# PCBSchematic.net
KiCad netlist of a schematic drawn in Altium Designer
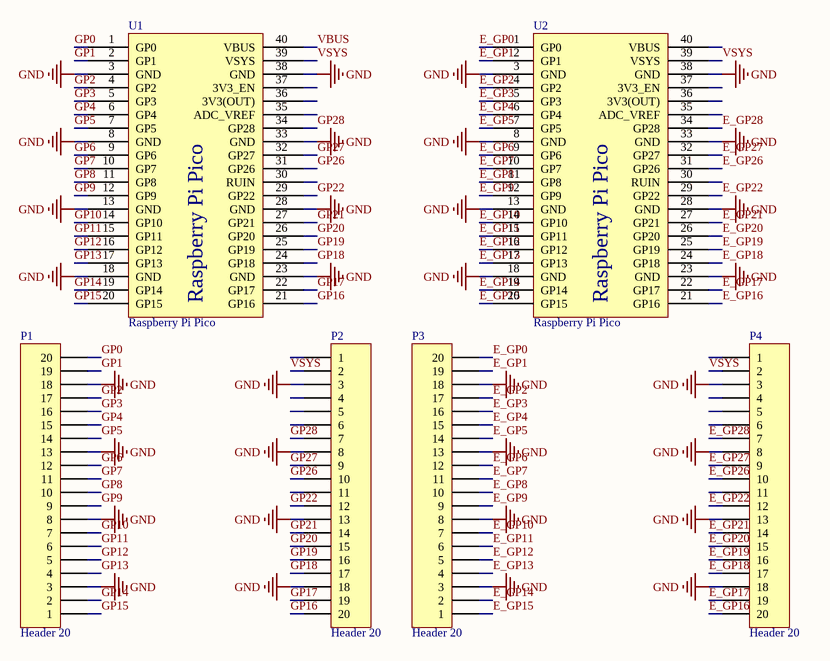
[diagram p0: PCBSchematic.SchDoc]

(export (version "E")
  (design (tool "Eeschema 10.0.6"))
  (components
    (comp (ref "P1")
      (value "Header 20")
      (footprint "HDR1X20")
      (description "Header, 20-Pin")
      (fields (field (name "PUBLISHER") "Altium Limited"))
      (libsource (lib "Miscellaneous Connectors") (part "Header 20"))
    )
    (comp (ref "P2")
      (value "Header 20")
      (footprint "HDR1X20")
      (description "Header, 20-Pin")
      (fields (field (name "PUBLISHER") "Altium Limited"))
      (libsource (lib "") (part "Header 20_1"))
    )
    (comp (ref "P3")
      (value "Header 20")
      (footprint "HDR1X20")
      (description "Header, 20-Pin")
      (fields (field (name "PUBLISHER") "Altium Limited"))
      (libsource (lib "Miscellaneous Connectors") (part "Header 20"))
    )
    (comp (ref "P4")
      (value "Header 20")
      (footprint "HDR1X20")
      (description "Header, 20-Pin")
      (fields (field (name "PUBLISHER") "Altium Limited"))
      (libsource (lib "") (part "Header 20_1"))
    )
    (comp (ref "U1")
      (value "Raspberry Pi Pico")
      (footprint "Raspberry Pi Pico")
      (libsource (lib "ECE Lib 22") (part "Raspberry Pi Pico"))
    )
    (comp (ref "U2")
      (value "Raspberry Pi Pico")
      (footprint "Raspberry Pi Pico")
      (libsource (lib "ECE Lib 22") (part "Raspberry Pi Pico"))
    )
  )
  (nets
    (net (code "1") (name "/E_GP0") (class "Default")
      (node (ref "P3") (pin "20") (pinfunction "20_20") (pintype "passive"))
      (node (ref "U2") (pin "1") (pinfunction "GP0_1") (pintype "passive"))
    )
    (net (code "2") (name "/E_GP1") (class "Default")
      (node (ref "P3") (pin "19") (pinfunction "19_19") (pintype "passive"))
      (node (ref "U2") (pin "2") (pinfunction "GP1_2") (pintype "passive"))
    )
    (net (code "3") (name "/E_GP2") (class "Default")
      (node (ref "P3") (pin "17") (pinfunction "17_17") (pintype "passive"))
      (node (ref "U2") (pin "4") (pinfunction "GP2_4") (pintype "passive"))
    )
    (net (code "4") (name "/E_GP3") (class "Default")
      (node (ref "P3") (pin "16") (pinfunction "16_16") (pintype "passive"))
      (node (ref "U2") (pin "5") (pinfunction "GP3_5") (pintype "passive"))
    )
    (net (code "5") (name "/E_GP4") (class "Default")
      (node (ref "P3") (pin "15") (pinfunction "15_15") (pintype "passive"))
      (node (ref "U2") (pin "6") (pinfunction "GP4_6") (pintype "passive"))
    )
    (net (code "6") (name "/E_GP5") (class "Default")
      (node (ref "P3") (pin "14") (pinfunction "14_14") (pintype "passive"))
      (node (ref "U2") (pin "7") (pinfunction "GP5_7") (pintype "passive"))
    )
    (net (code "7") (name "/E_GP6") (class "Default")
      (node (ref "P3") (pin "12") (pinfunction "12_12") (pintype "passive"))
      (node (ref "U2") (pin "9") (pinfunction "GP6_9") (pintype "passive"))
    )
    (net (code "8") (name "/E_GP7") (class "Default")
      (node (ref "P3") (pin "11") (pinfunction "11_11") (pintype "passive"))
      (node (ref "U2") (pin "10") (pinfunction "GP7_10") (pintype "passive"))
    )
    (net (code "9") (name "/E_GP8") (class "Default")
      (node (ref "P3") (pin "10") (pinfunction "10_10") (pintype "passive"))
      (node (ref "U2") (pin "11") (pinfunction "GP8_11") (pintype "passive"))
    )
    (net (code "10") (name "/E_GP9") (class "Default")
      (node (ref "P3") (pin "9") (pinfunction "9_9") (pintype "passive"))
      (node (ref "U2") (pin "12") (pinfunction "GP9_12") (pintype "passive"))
    )
    (net (code "11") (name "/E_GP10") (class "Default")
      (node (ref "P3") (pin "7") (pinfunction "7_7") (pintype "passive"))
      (node (ref "U2") (pin "14") (pinfunction "GP10_14") (pintype "passive"))
    )
    (net (code "12") (name "/E_GP11") (class "Default")
      (node (ref "P3") (pin "6") (pinfunction "6_6") (pintype "passive"))
      (node (ref "U2") (pin "15") (pinfunction "GP11_15") (pintype "passive"))
    )
    (net (code "13") (name "/E_GP12") (class "Default")
      (node (ref "P3") (pin "5") (pinfunction "5_5") (pintype "passive"))
      (node (ref "U2") (pin "16") (pinfunction "GP12_16") (pintype "passive"))
    )
    (net (code "14") (name "/E_GP13") (class "Default")
      (node (ref "P3") (pin "4") (pinfunction "4_4") (pintype "passive"))
      (node (ref "U2") (pin "17") (pinfunction "GP13_17") (pintype "passive"))
    )
    (net (code "15") (name "/E_GP14") (class "Default")
      (node (ref "P3") (pin "2") (pinfunction "2_2") (pintype "passive"))
      (node (ref "U2") (pin "19") (pinfunction "GP14_19") (pintype "passive"))
    )
    (net (code "16") (name "/E_GP15") (class "Default")
      (node (ref "P3") (pin "1") (pinfunction "1_1") (pintype "passive"))
      (node (ref "U2") (pin "20") (pinfunction "GP15_20") (pintype "passive"))
    )
    (net (code "17") (name "/E_GP16") (class "Default")
      (node (ref "P4") (pin "20") (pinfunction "20_20") (pintype "passive"))
      (node (ref "U2") (pin "21") (pinfunction "GP16_21") (pintype "passive"))
    )
    (net (code "18") (name "/E_GP17") (class "Default")
      (node (ref "P4") (pin "19") (pinfunction "19_19") (pintype "passive"))
      (node (ref "U2") (pin "22") (pinfunction "GP17_22") (pintype "passive"))
    )
    (net (code "19") (name "/E_GP18") (class "Default")
      (node (ref "P4") (pin "17") (pinfunction "17_17") (pintype "passive"))
      (node (ref "U2") (pin "24") (pinfunction "GP18_24") (pintype "passive"))
    )
    (net (code "20") (name "/E_GP19") (class "Default")
      (node (ref "P4") (pin "16") (pinfunction "16_16") (pintype "passive"))
      (node (ref "U2") (pin "25") (pinfunction "GP19_25") (pintype "passive"))
    )
    (net (code "21") (name "/E_GP20") (class "Default")
      (node (ref "P4") (pin "15") (pinfunction "15_15") (pintype "passive"))
      (node (ref "U2") (pin "26") (pinfunction "GP20_26") (pintype "passive"))
    )
    (net (code "22") (name "/E_GP21") (class "Default")
      (node (ref "P4") (pin "14") (pinfunction "14_14") (pintype "passive"))
      (node (ref "U2") (pin "27") (pinfunction "GP21_27") (pintype "passive"))
    )
    (net (code "23") (name "/E_GP22") (class "Default")
      (node (ref "P4") (pin "12") (pinfunction "12_12") (pintype "passive"))
      (node (ref "U2") (pin "29") (pinfunction "GP22_29") (pintype "passive"))
    )
    (net (code "24") (name "/E_GP26") (class "Default")
      (node (ref "P4") (pin "10") (pinfunction "10_10") (pintype "passive"))
      (node (ref "U2") (pin "31") (pinfunction "GP26_31") (pintype "passive"))
    )
    (net (code "25") (name "/E_GP27") (class "Default")
      (node (ref "P4") (pin "9") (pinfunction "9_9") (pintype "passive"))
      (node (ref "U2") (pin "32") (pinfunction "GP27_32") (pintype "passive"))
    )
    (net (code "26") (name "/E_GP28") (class "Default")
      (node (ref "P4") (pin "7") (pinfunction "7_7") (pintype "passive"))
      (node (ref "U2") (pin "34") (pinfunction "GP28_34") (pintype "passive"))
    )
    (net (code "27") (name "/GP0") (class "Default")
      (node (ref "P1") (pin "20") (pinfunction "20_20") (pintype "passive"))
      (node (ref "U1") (pin "1") (pinfunction "GP0_1") (pintype "passive"))
    )
    (net (code "28") (name "/GP1") (class "Default")
      (node (ref "P1") (pin "19") (pinfunction "19_19") (pintype "passive"))
      (node (ref "U1") (pin "2") (pinfunction "GP1_2") (pintype "passive"))
    )
    (net (code "29") (name "/GP2") (class "Default")
      (node (ref "P1") (pin "17") (pinfunction "17_17") (pintype "passive"))
      (node (ref "U1") (pin "4") (pinfunction "GP2_4") (pintype "passive"))
    )
    (net (code "30") (name "/GP3") (class "Default")
      (node (ref "P1") (pin "16") (pinfunction "16_16") (pintype "passive"))
      (node (ref "U1") (pin "5") (pinfunction "GP3_5") (pintype "passive"))
    )
    (net (code "31") (name "/GP4") (class "Default")
      (node (ref "P1") (pin "15") (pinfunction "15_15") (pintype "passive"))
      (node (ref "U1") (pin "6") (pinfunction "GP4_6") (pintype "passive"))
    )
    (net (code "32") (name "/GP5") (class "Default")
      (node (ref "P1") (pin "14") (pinfunction "14_14") (pintype "passive"))
      (node (ref "U1") (pin "7") (pinfunction "GP5_7") (pintype "passive"))
    )
    (net (code "33") (name "/GP6") (class "Default")
      (node (ref "P1") (pin "12") (pinfunction "12_12") (pintype "passive"))
      (node (ref "U1") (pin "9") (pinfunction "GP6_9") (pintype "passive"))
    )
    (net (code "34") (name "/GP7") (class "Default")
      (node (ref "P1") (pin "11") (pinfunction "11_11") (pintype "passive"))
      (node (ref "U1") (pin "10") (pinfunction "GP7_10") (pintype "passive"))
    )
    (net (code "35") (name "/GP8") (class "Default")
      (node (ref "P1") (pin "10") (pinfunction "10_10") (pintype "passive"))
      (node (ref "U1") (pin "11") (pinfunction "GP8_11") (pintype "passive"))
    )
    (net (code "36") (name "/GP9") (class "Default")
      (node (ref "P1") (pin "9") (pinfunction "9_9") (pintype "passive"))
      (node (ref "U1") (pin "12") (pinfunction "GP9_12") (pintype "passive"))
    )
    (net (code "37") (name "/GP10") (class "Default")
      (node (ref "P1") (pin "7") (pinfunction "7_7") (pintype "passive"))
      (node (ref "U1") (pin "14") (pinfunction "GP10_14") (pintype "passive"))
    )
    (net (code "38") (name "/GP11") (class "Default")
      (node (ref "P1") (pin "6") (pinfunction "6_6") (pintype "passive"))
      (node (ref "U1") (pin "15") (pinfunction "GP11_15") (pintype "passive"))
    )
    (net (code "39") (name "/GP12") (class "Default")
      (node (ref "P1") (pin "5") (pinfunction "5_5") (pintype "passive"))
      (node (ref "U1") (pin "16") (pinfunction "GP12_16") (pintype "passive"))
    )
    (net (code "40") (name "/GP13") (class "Default")
      (node (ref "P1") (pin "4") (pinfunction "4_4") (pintype "passive"))
      (node (ref "U1") (pin "17") (pinfunction "GP13_17") (pintype "passive"))
    )
    (net (code "41") (name "/GP14") (class "Default")
      (node (ref "P1") (pin "2") (pinfunction "2_2") (pintype "passive"))
      (node (ref "U1") (pin "19") (pinfunction "GP14_19") (pintype "passive"))
    )
    (net (code "42") (name "/GP15") (class "Default")
      (node (ref "P1") (pin "1") (pinfunction "1_1") (pintype "passive"))
      (node (ref "U1") (pin "20") (pinfunction "GP15_20") (pintype "passive"))
    )
    (net (code "43") (name "/GP16") (class "Default")
      (node (ref "P2") (pin "20") (pinfunction "20_20") (pintype "passive"))
      (node (ref "U1") (pin "21") (pinfunction "GP16_21") (pintype "passive"))
    )
    (net (code "44") (name "/GP17") (class "Default")
      (node (ref "P2") (pin "19") (pinfunction "19_19") (pintype "passive"))
      (node (ref "U1") (pin "22") (pinfunction "GP17_22") (pintype "passive"))
    )
    (net (code "45") (name "/GP18") (class "Default")
      (node (ref "P2") (pin "17") (pinfunction "17_17") (pintype "passive"))
      (node (ref "U1") (pin "24") (pinfunction "GP18_24") (pintype "passive"))
    )
    (net (code "46") (name "/GP19") (class "Default")
      (node (ref "P2") (pin "16") (pinfunction "16_16") (pintype "passive"))
      (node (ref "U1") (pin "25") (pinfunction "GP19_25") (pintype "passive"))
    )
    (net (code "47") (name "/GP20") (class "Default")
      (node (ref "P2") (pin "15") (pinfunction "15_15") (pintype "passive"))
      (node (ref "U1") (pin "26") (pinfunction "GP20_26") (pintype "passive"))
    )
    (net (code "48") (name "/GP21") (class "Default")
      (node (ref "P2") (pin "14") (pinfunction "14_14") (pintype "passive"))
      (node (ref "U1") (pin "27") (pinfunction "GP21_27") (pintype "passive"))
    )
    (net (code "49") (name "/GP22") (class "Default")
      (node (ref "P2") (pin "12") (pinfunction "12_12") (pintype "passive"))
      (node (ref "U1") (pin "29") (pinfunction "GP22_29") (pintype "passive"))
    )
    (net (code "50") (name "/GP26") (class "Default")
      (node (ref "P2") (pin "10") (pinfunction "10_10") (pintype "passive"))
      (node (ref "U1") (pin "31") (pinfunction "GP26_31") (pintype "passive"))
    )
    (net (code "51") (name "/GP27") (class "Default")
      (node (ref "P2") (pin "9") (pinfunction "9_9") (pintype "passive"))
      (node (ref "U1") (pin "32") (pinfunction "GP27_32") (pintype "passive"))
    )
    (net (code "52") (name "/GP28") (class "Default")
      (node (ref "P2") (pin "7") (pinfunction "7_7") (pintype "passive"))
      (node (ref "U1") (pin "34") (pinfunction "GP28_34") (pintype "passive"))
    )
    (net (code "53") (name "/VBUS") (class "Default")
      (node (ref "U1") (pin "40") (pinfunction "VBUS_40") (pintype "passive"))
    )
    (net (code "54") (name "/VSYS") (class "Default")
      (node (ref "P2") (pin "2") (pinfunction "2_2") (pintype "passive"))
      (node (ref "P4") (pin "2") (pinfunction "2_2") (pintype "passive"))
      (node (ref "U1") (pin "39") (pinfunction "VSYS_39") (pintype "passive"))
      (node (ref "U2") (pin "39") (pinfunction "VSYS_39") (pintype "passive"))
    )
    (net (code "55") (name "GND") (class "Default")
      (node (ref "P1") (pin "13") (pinfunction "13_13") (pintype "passive"))
      (node (ref "P1") (pin "18") (pinfunction "18_18") (pintype "passive"))
      (node (ref "P1") (pin "3") (pinfunction "3_3") (pintype "passive"))
      (node (ref "P1") (pin "8") (pinfunction "8_8") (pintype "passive"))
      (node (ref "P2") (pin "13") (pinfunction "13_13") (pintype "passive"))
      (node (ref "P2") (pin "18") (pinfunction "18_18") (pintype "passive"))
      (node (ref "P2") (pin "3") (pinfunction "3_3") (pintype "passive"))
      (node (ref "P2") (pin "8") (pinfunction "8_8") (pintype "passive"))
      (node (ref "P3") (pin "13") (pinfunction "13_13") (pintype "passive"))
      (node (ref "P3") (pin "18") (pinfunction "18_18") (pintype "passive"))
      (node (ref "P3") (pin "3") (pinfunction "3_3") (pintype "passive"))
      (node (ref "P3") (pin "8") (pinfunction "8_8") (pintype "passive"))
      (node (ref "P4") (pin "13") (pinfunction "13_13") (pintype "passive"))
      (node (ref "P4") (pin "18") (pinfunction "18_18") (pintype "passive"))
      (node (ref "P4") (pin "3") (pinfunction "3_3") (pintype "passive"))
      (node (ref "P4") (pin "8") (pinfunction "8_8") (pintype "passive"))
      (node (ref "U1") (pin "13") (pinfunction "GND_13") (pintype "passive"))
      (node (ref "U1") (pin "18") (pinfunction "GND_18") (pintype "passive"))
      (node (ref "U1") (pin "23") (pinfunction "GND_23") (pintype "passive"))
      (node (ref "U1") (pin "28") (pinfunction "GND_28") (pintype "passive"))
      (node (ref "U1") (pin "3") (pinfunction "GND_3") (pintype "passive"))
      (node (ref "U1") (pin "33") (pinfunction "GND_33") (pintype "passive"))
      (node (ref "U1") (pin "38") (pinfunction "GND_38") (pintype "passive"))
      (node (ref "U1") (pin "8") (pinfunction "GND_8") (pintype "passive"))
      (node (ref "U2") (pin "13") (pinfunction "GND_13") (pintype "passive"))
      (node (ref "U2") (pin "18") (pinfunction "GND_18") (pintype "passive"))
      (node (ref "U2") (pin "23") (pinfunction "GND_23") (pintype "passive"))
      (node (ref "U2") (pin "28") (pinfunction "GND_28") (pintype "passive"))
      (node (ref "U2") (pin "3") (pinfunction "GND_3") (pintype "passive"))
      (node (ref "U2") (pin "33") (pinfunction "GND_33") (pintype "passive"))
      (node (ref "U2") (pin "38") (pinfunction "GND_38") (pintype "passive"))
      (node (ref "U2") (pin "8") (pinfunction "GND_8") (pintype "passive"))
    )
    (net (code "56") (name "unconnected-(P2-Pad1)") (class "Default")
      (node (ref "P2") (pin "1") (pinfunction "1_1") (pintype "passive"))
    )
    (net (code "57") (name "unconnected-(P2-Pad4)") (class "Default")
      (node (ref "P2") (pin "4") (pinfunction "4_4") (pintype "passive"))
    )
    (net (code "58") (name "unconnected-(P2-Pad5)") (class "Default")
      (node (ref "P2") (pin "5") (pinfunction "5_5") (pintype "passive"))
    )
    (net (code "59") (name "unconnected-(P2-Pad6)") (class "Default")
      (node (ref "P2") (pin "6") (pinfunction "6_6") (pintype "passive"))
    )
    (net (code "60") (name "unconnected-(P2-Pad11)") (class "Default")
      (node (ref "P2") (pin "11") (pinfunction "11_11") (pintype "passive"))
    )
    (net (code "61") (name "unconnected-(P4-Pad1)") (class "Default")
      (node (ref "P4") (pin "1") (pinfunction "1_1") (pintype "passive"))
    )
    (net (code "62") (name "unconnected-(P4-Pad4)") (class "Default")
      (node (ref "P4") (pin "4") (pinfunction "4_4") (pintype "passive"))
    )
    (net (code "63") (name "unconnected-(P4-Pad5)") (class "Default")
      (node (ref "P4") (pin "5") (pinfunction "5_5") (pintype "passive"))
    )
    (net (code "64") (name "unconnected-(P4-Pad6)") (class "Default")
      (node (ref "P4") (pin "6") (pinfunction "6_6") (pintype "passive"))
    )
    (net (code "65") (name "unconnected-(P4-Pad11)") (class "Default")
      (node (ref "P4") (pin "11") (pinfunction "11_11") (pintype "passive"))
    )
    (net (code "66") (name "unconnected-(U1-3V3(OUT)-Pad36)") (class "Default")
      (node (ref "U1") (pin "36") (pinfunction "3V3(OUT)_36") (pintype "passive"))
    )
    (net (code "67") (name "unconnected-(U1-3V3_EN-Pad37)") (class "Default")
      (node (ref "U1") (pin "37") (pinfunction "3V3_EN_37") (pintype "passive"))
    )
    (net (code "68") (name "unconnected-(U1-ADC_VREF-Pad35)") (class "Default")
      (node (ref "U1") (pin "35") (pinfunction "ADC_VREF_35") (pintype "passive"))
    )
    (net (code "69") (name "unconnected-(U1-RUIN-Pad30)") (class "Default")
      (node (ref "U1") (pin "30") (pinfunction "RUIN_30") (pintype "passive"))
    )
    (net (code "70") (name "unconnected-(U2-3V3(OUT)-Pad36)") (class "Default")
      (node (ref "U2") (pin "36") (pinfunction "3V3(OUT)_36") (pintype "passive"))
    )
    (net (code "71") (name "unconnected-(U2-3V3_EN-Pad37)") (class "Default")
      (node (ref "U2") (pin "37") (pinfunction "3V3_EN_37") (pintype "passive"))
    )
    (net (code "72") (name "unconnected-(U2-ADC_VREF-Pad35)") (class "Default")
      (node (ref "U2") (pin "35") (pinfunction "ADC_VREF_35") (pintype "passive"))
    )
    (net (code "73") (name "unconnected-(U2-RUIN-Pad30)") (class "Default")
      (node (ref "U2") (pin "30") (pinfunction "RUIN_30") (pintype "passive"))
    )
    (net (code "74") (name "unconnected-(U2-VBUS-Pad40)") (class "Default")
      (node (ref "U2") (pin "40") (pinfunction "VBUS_40") (pintype "passive"))
    )
  )
)
